# connect_4_v2.net
KiCad netlist of a schematic drawn in EasyEDA
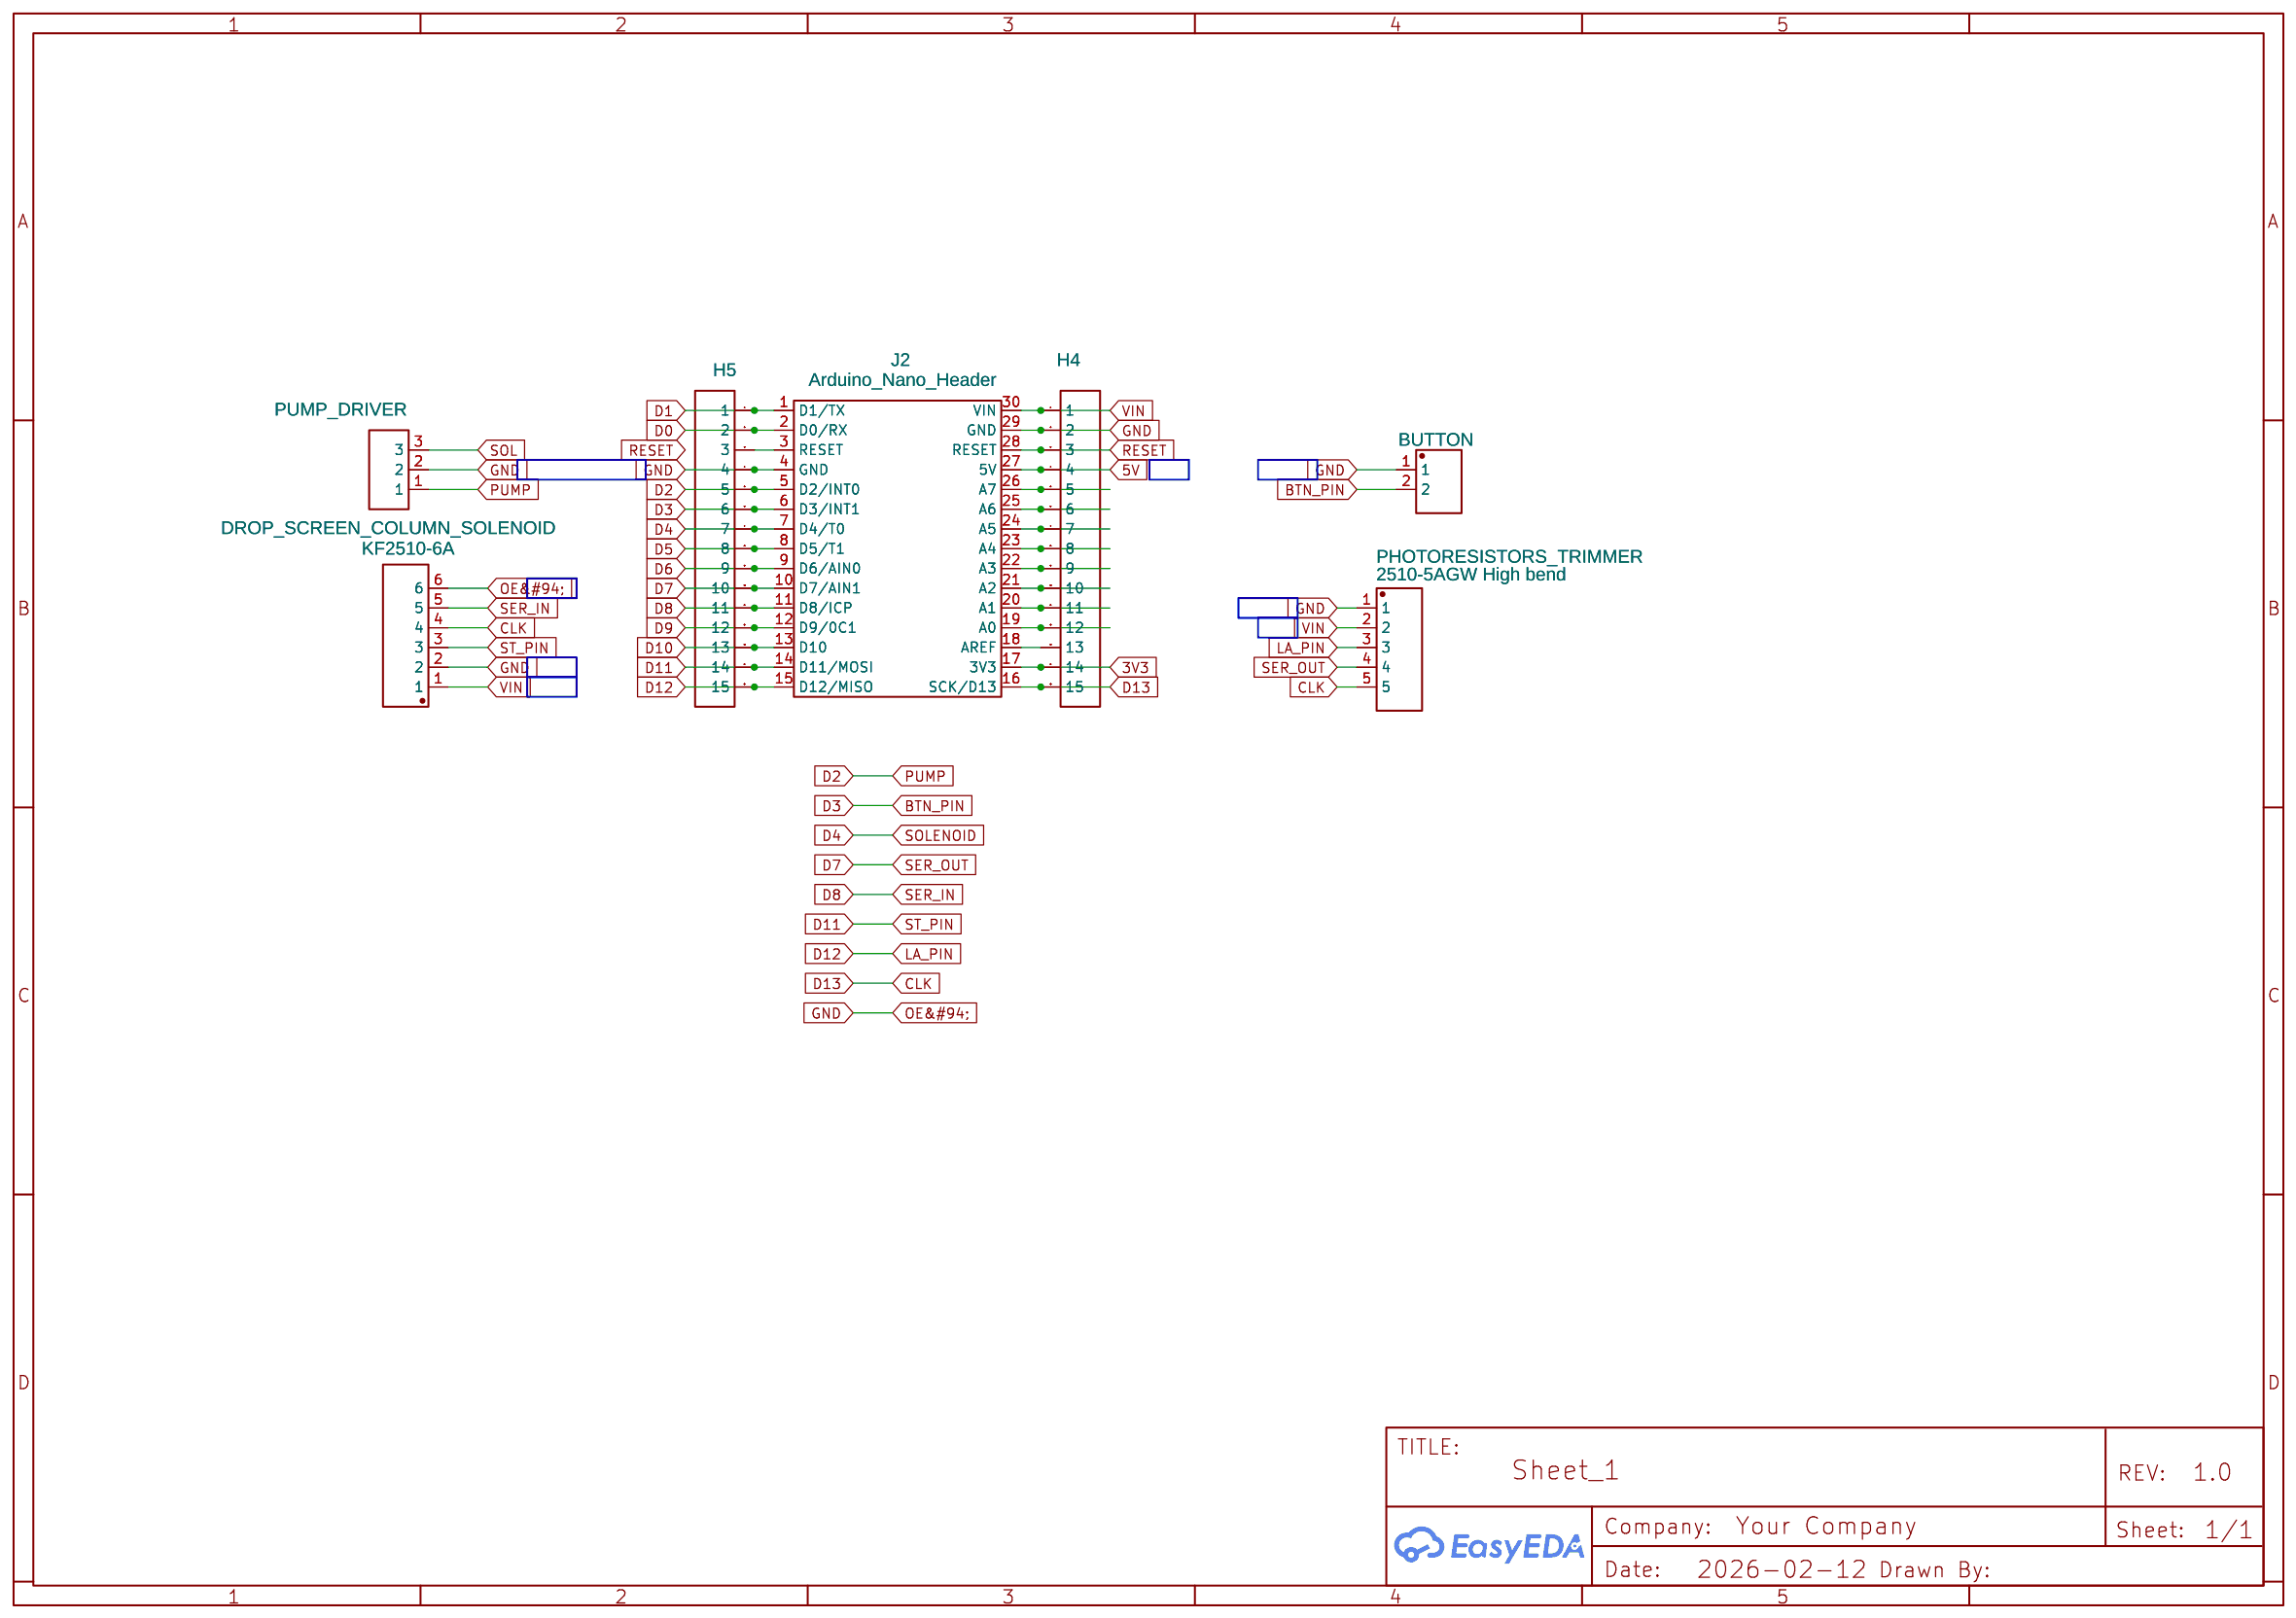
[diagram p0: schematic sheet]

(export (version "E")
  (design (tool "Eeschema 10.0.6"))
  (components
    (comp (ref "D3")
      (value "BUTTON")
      (fields (field (name "Manufacturer Part") "KF2510-2A") (field (name "Manufacturer") "BOOMELE"))
      (libsource (lib "") (part "KF2510-2A"))
    )
    (comp (ref "DROP_SCREEN_COLUMN_SOLENOID")
      (value "KF2510-6A")
      (fields (field (name "Manufacturer Part") "KF2510-6A针座"))
      (libsource (lib "") (part "KF2510-6A"))
    )
    (comp (ref "H4") (value "HDR-F-2.54_1x15") (libsource (lib "") (part "HDR-F-2.54_1x15")))
    (comp (ref "H5") (value "HDR-F-2.54_1x15") (libsource (lib "") (part "HDR-F-2.54_1x15_1")))
    (comp (ref "J2") (value "Arduino_Nano_Header") (libsource (lib "") (part "Arduino_Nano_Header")))
    (comp (ref "PHOTORESISTORS_TRIMMER")
      (value "2510-5AGW High bend")
      (fields (field (name "Manufacturer Part") "2510-5A高弯") (field (name "Manufacturer") "BOOMELE(博穆精密)"))
      (libsource (lib "") (part "2510-5AGW High bend"))
    )
    (comp (ref "PUMP_DRIVER") (value "FK2510") (libsource (lib "") (part "kf2510_3A")))
  )
  (nets
    (net (code "1") (name "3V3") (class "Default")
      (node (ref "H4") (pin "14") (pinfunction "14_14") (pintype "unspecified"))
      (node (ref "J2") (pin "17") (pinfunction "3V3_17") (pintype "unspecified"))
    )
    (net (code "2") (name "5V") (class "Default")
      (node (ref "H4") (pin "4") (pinfunction "4_4") (pintype "unspecified"))
      (node (ref "J2") (pin "27") (pinfunction "5V_27") (pintype "unspecified"))
    )
    (net (code "3") (name "BTN_PIN") (class "Default")
      (node (ref "D3") (pin "2") (pinfunction "2_2") (pintype "unspecified"))
      (node (ref "H5") (pin "6") (pinfunction "6_6") (pintype "unspecified"))
      (node (ref "J2") (pin "6") (pinfunction "D3/INT1_6") (pintype "unspecified"))
    )
    (net (code "4") (name "CLK") (class "Default")
      (node (ref "DROP_SCREEN_COLUMN_SOLENOID") (pin "4") (pinfunction "4_4") (pintype "unspecified"))
      (node (ref "H4") (pin "15") (pinfunction "15_15") (pintype "unspecified"))
      (node (ref "J2") (pin "16") (pinfunction "SCK/D13_16") (pintype "unspecified"))
      (node (ref "PHOTORESISTORS_TRIMMER") (pin "5") (pinfunction "5_5") (pintype "unspecified"))
    )
    (net (code "5") (name "D0") (class "Default")
      (node (ref "H5") (pin "2") (pinfunction "2_2") (pintype "unspecified"))
      (node (ref "J2") (pin "2") (pinfunction "D0/RX_2") (pintype "unspecified"))
    )
    (net (code "6") (name "D1") (class "Default")
      (node (ref "H5") (pin "1") (pinfunction "1_1") (pintype "unspecified"))
      (node (ref "J2") (pin "1") (pinfunction "D1/TX_1") (pintype "unspecified"))
    )
    (net (code "7") (name "D2") (class "Default")
      (node (ref "H5") (pin "5") (pinfunction "5_5") (pintype "unspecified"))
      (node (ref "J2") (pin "5") (pinfunction "D2/INT0_5") (pintype "unspecified"))
      (node (ref "PUMP_DRIVER") (pin "1") (pinfunction "1_1") (pintype "unspecified"))
    )
    (net (code "8") (name "D4") (class "Default")
      (node (ref "H5") (pin "7") (pinfunction "7_7") (pintype "unspecified"))
      (node (ref "J2") (pin "7") (pinfunction "D4/T0_7") (pintype "unspecified"))
    )
    (net (code "9") (name "D5") (class "Default")
      (node (ref "H5") (pin "8") (pinfunction "8_8") (pintype "unspecified"))
      (node (ref "J2") (pin "8") (pinfunction "D5/T1_8") (pintype "unspecified"))
    )
    (net (code "10") (name "D6") (class "Default")
      (node (ref "H5") (pin "9") (pinfunction "9_9") (pintype "unspecified"))
      (node (ref "J2") (pin "9") (pinfunction "D6/AIN0_9") (pintype "unspecified"))
    )
    (net (code "11") (name "D7") (class "Default")
      (node (ref "H5") (pin "10") (pinfunction "10_10") (pintype "unspecified"))
      (node (ref "J2") (pin "10") (pinfunction "D7/AIN1_10") (pintype "unspecified"))
      (node (ref "PHOTORESISTORS_TRIMMER") (pin "4") (pinfunction "4_4") (pintype "unspecified"))
    )
    (net (code "12") (name "D8") (class "Default")
      (node (ref "DROP_SCREEN_COLUMN_SOLENOID") (pin "5") (pinfunction "5_5") (pintype "unspecified"))
      (node (ref "H5") (pin "11") (pinfunction "11_11") (pintype "unspecified"))
      (node (ref "J2") (pin "11") (pinfunction "D8/ICP_11") (pintype "unspecified"))
    )
    (net (code "13") (name "D9") (class "Default")
      (node (ref "H5") (pin "12") (pinfunction "12_12") (pintype "unspecified"))
      (node (ref "J2") (pin "12") (pinfunction "D9/0C1_12") (pintype "unspecified"))
    )
    (net (code "14") (name "D10") (class "Default")
      (node (ref "H5") (pin "13") (pinfunction "13_13") (pintype "unspecified"))
      (node (ref "J2") (pin "13") (pinfunction "D10_13") (pintype "unspecified"))
    )
    (net (code "15") (name "D11") (class "Default")
      (node (ref "DROP_SCREEN_COLUMN_SOLENOID") (pin "3") (pinfunction "3_3") (pintype "unspecified"))
      (node (ref "H5") (pin "14") (pinfunction "14_14") (pintype "unspecified"))
      (node (ref "J2") (pin "14") (pinfunction "D11/MOSI_14") (pintype "unspecified"))
    )
    (net (code "16") (name "D12") (class "Default")
      (node (ref "H5") (pin "15") (pinfunction "15_15") (pintype "unspecified"))
      (node (ref "J2") (pin "15") (pinfunction "D12/MISO_15") (pintype "unspecified"))
      (node (ref "PHOTORESISTORS_TRIMMER") (pin "3") (pinfunction "3_3") (pintype "unspecified"))
    )
    (net (code "17") (name "GND") (class "Default")
      (node (ref "D3") (pin "1") (pinfunction "1_1") (pintype "unspecified"))
      (node (ref "DROP_SCREEN_COLUMN_SOLENOID") (pin "2") (pinfunction "2_2") (pintype "unspecified"))
      (node (ref "DROP_SCREEN_COLUMN_SOLENOID") (pin "6") (pinfunction "6_6") (pintype "unspecified"))
      (node (ref "H4") (pin "2") (pinfunction "2_2") (pintype "unspecified"))
      (node (ref "H5") (pin "4") (pinfunction "4_4") (pintype "unspecified"))
      (node (ref "J2") (pin "29") (pinfunction "GND_29") (pintype "unspecified"))
      (node (ref "J2") (pin "4") (pinfunction "GND_4") (pintype "unspecified"))
      (node (ref "PHOTORESISTORS_TRIMMER") (pin "1") (pinfunction "1_1") (pintype "unspecified"))
      (node (ref "PUMP_DRIVER") (pin "2") (pinfunction "2_2") (pintype "unspecified"))
    )
    (net (code "18") (name "Net-(H5-Pad3)") (class "Default")
      (node (ref "H5") (pin "3") (pinfunction "3_3") (pintype "unspecified"))
      (node (ref "J2") (pin "3") (pinfunction "RESET_3") (pintype "unspecified"))
    )
    (net (code "19") (name "Net-(J2-A0)") (class "Default")
      (node (ref "H4") (pin "12") (pinfunction "12_12") (pintype "unspecified"))
      (node (ref "J2") (pin "19") (pinfunction "A0_19") (pintype "unspecified"))
    )
    (net (code "20") (name "Net-(J2-A1)") (class "Default")
      (node (ref "H4") (pin "11") (pinfunction "11_11") (pintype "unspecified"))
      (node (ref "J2") (pin "20") (pinfunction "A1_20") (pintype "unspecified"))
    )
    (net (code "21") (name "Net-(J2-A2)") (class "Default")
      (node (ref "H4") (pin "10") (pinfunction "10_10") (pintype "unspecified"))
      (node (ref "J2") (pin "21") (pinfunction "A2_21") (pintype "unspecified"))
    )
    (net (code "22") (name "Net-(J2-A3)") (class "Default")
      (node (ref "H4") (pin "9") (pinfunction "9_9") (pintype "unspecified"))
      (node (ref "J2") (pin "22") (pinfunction "A3_22") (pintype "unspecified"))
    )
    (net (code "23") (name "Net-(J2-A4)") (class "Default")
      (node (ref "H4") (pin "8") (pinfunction "8_8") (pintype "unspecified"))
      (node (ref "J2") (pin "23") (pinfunction "A4_23") (pintype "unspecified"))
    )
    (net (code "24") (name "Net-(J2-A5)") (class "Default")
      (node (ref "H4") (pin "7") (pinfunction "7_7") (pintype "unspecified"))
      (node (ref "J2") (pin "24") (pinfunction "A5_24") (pintype "unspecified"))
    )
    (net (code "25") (name "Net-(J2-A6)") (class "Default")
      (node (ref "H4") (pin "6") (pinfunction "6_6") (pintype "unspecified"))
      (node (ref "J2") (pin "25") (pinfunction "A6_25") (pintype "unspecified"))
    )
    (net (code "26") (name "Net-(J2-A7)") (class "Default")
      (node (ref "H4") (pin "5") (pinfunction "5_5") (pintype "unspecified"))
      (node (ref "J2") (pin "26") (pinfunction "A7_26") (pintype "unspecified"))
    )
    (net (code "27") (name "Net-(J2-AREF)") (class "Default")
      (node (ref "H4") (pin "13") (pinfunction "13_13") (pintype "unspecified"))
      (node (ref "J2") (pin "18") (pinfunction "AREF_18") (pintype "unspecified"))
    )
    (net (code "28") (name "RESET") (class "Default")
      (node (ref "H4") (pin "3") (pinfunction "3_3") (pintype "unspecified"))
      (node (ref "J2") (pin "28") (pinfunction "RESET_28") (pintype "unspecified"))
    )
    (net (code "29") (name "SOL") (class "Default")
      (node (ref "PUMP_DRIVER") (pin "3") (pinfunction "3_3") (pintype "unspecified"))
    )
    (net (code "30") (name "VIN") (class "Default")
      (node (ref "DROP_SCREEN_COLUMN_SOLENOID") (pin "1") (pinfunction "1_1") (pintype "unspecified"))
      (node (ref "H4") (pin "1") (pinfunction "1_1") (pintype "unspecified"))
      (node (ref "J2") (pin "30") (pinfunction "VIN_30") (pintype "unspecified"))
      (node (ref "PHOTORESISTORS_TRIMMER") (pin "2") (pinfunction "2_2") (pintype "unspecified"))
    )
  )
)
